# dfp1.net
KiCad netlist of a schematic drawn in EAGLE
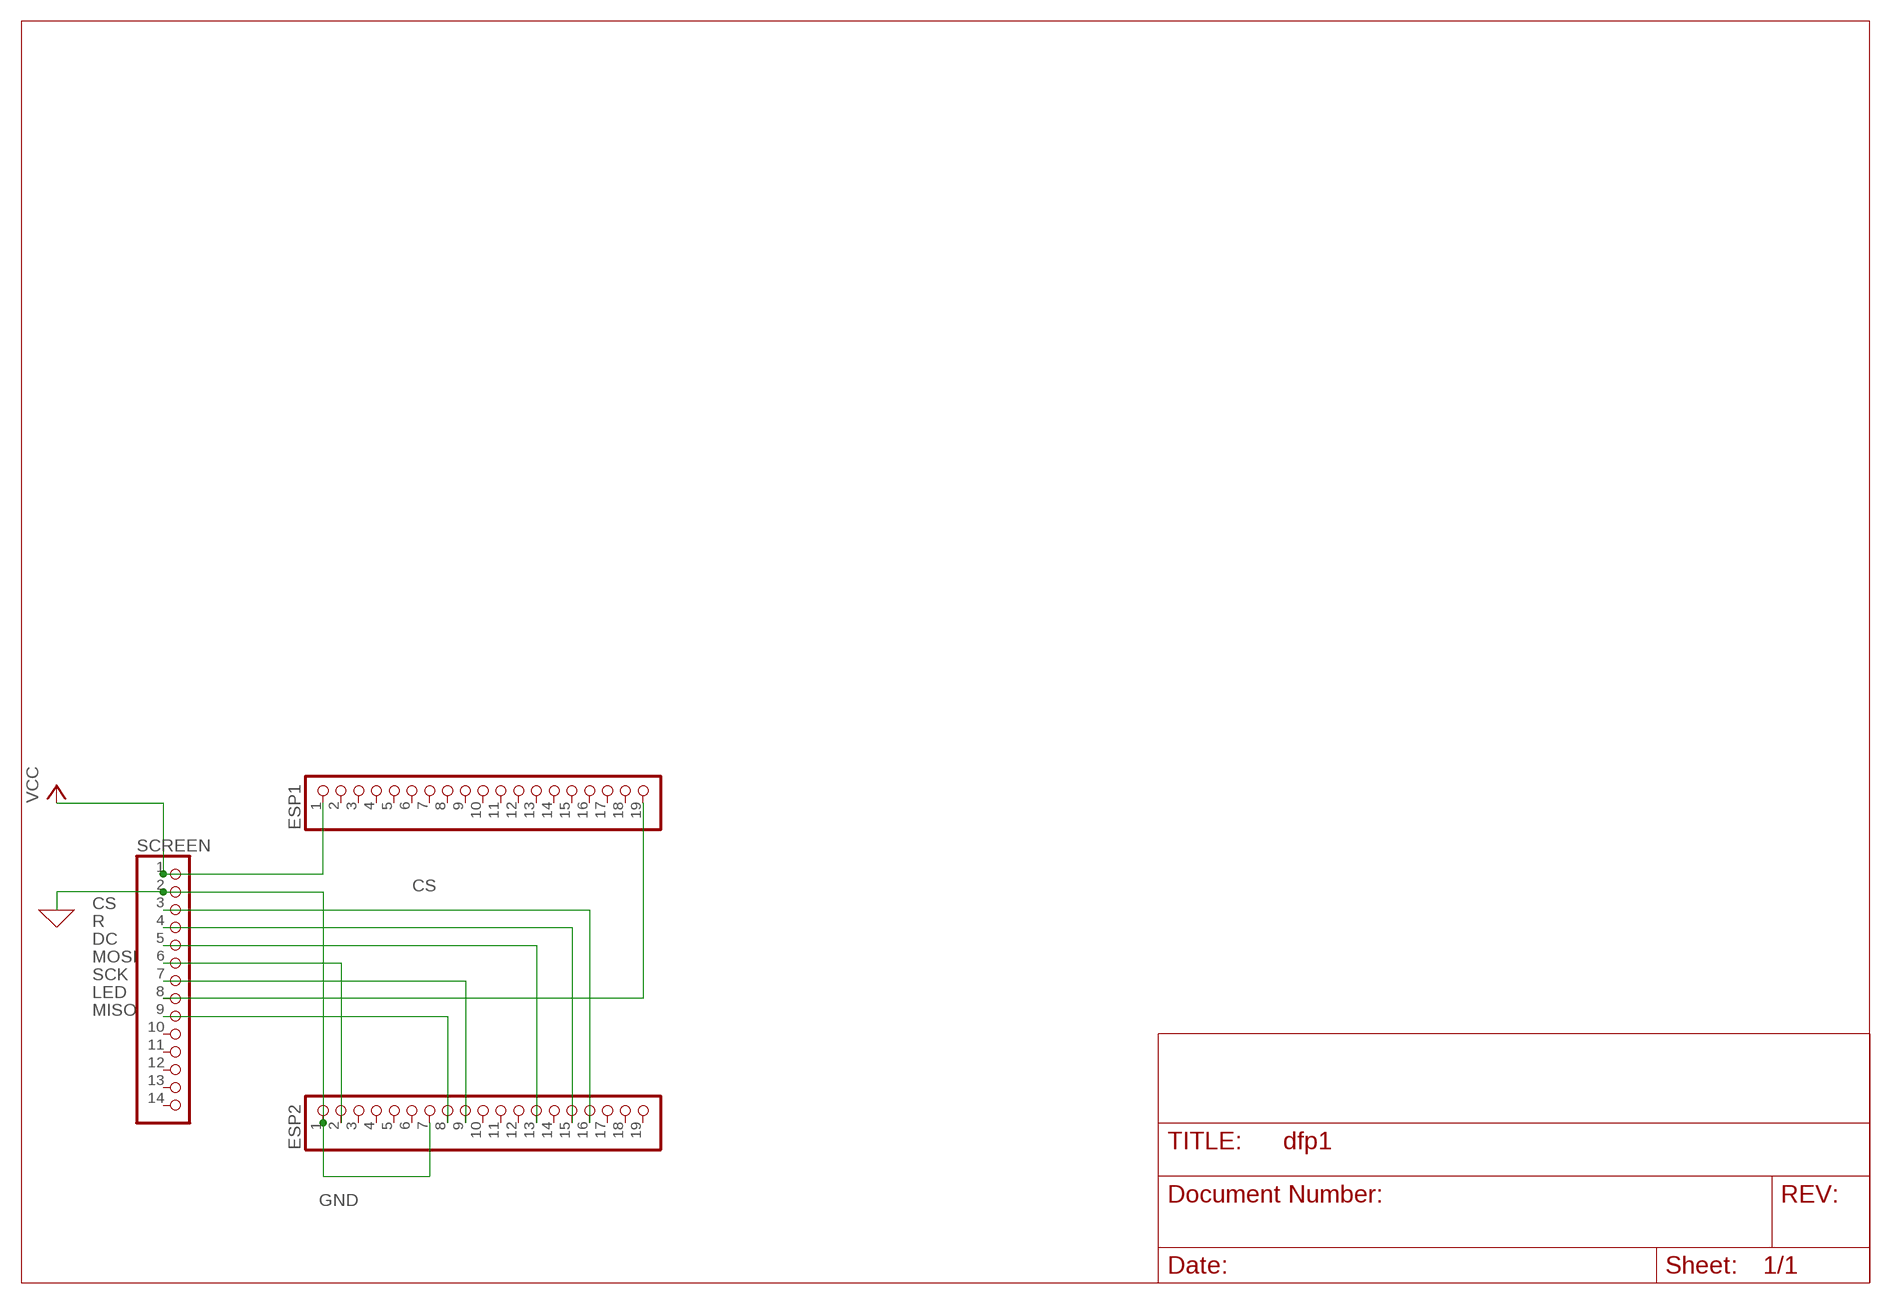
[diagram p0: schematic, sheet 1]

(export (version "E")
  (design (tool "Eeschema 10.0.6"))
  (components
    (comp (ref "ESP1")
      (value "PINHD-1X19")
      (footprint "eagle-import:1X19")
      (libsource (lib "eagle-import") (part "PINHD-1X19"))
    )
    (comp (ref "ESP2")
      (value "PINHD-1X19")
      (footprint "eagle-import:1X19")
      (libsource (lib "eagle-import") (part "PINHD-1X19"))
    )
    (comp (ref "SCREEN")
      (value "PINHD-1X14")
      (footprint "eagle-import:1X14")
      (libsource (lib "eagle-import") (part "PINHD-1X14"))
    )
  )
  (nets
    (net (code "1") (name "/CS") (class "Default")
      (node (ref "ESP2") (pin "16") (pinfunction "16_16") (pintype "passive"))
      (node (ref "SCREEN") (pin "3") (pinfunction "3_3") (pintype "passive"))
    )
    (net (code "2") (name "/DC") (class "Default")
      (node (ref "ESP2") (pin "13") (pinfunction "13_13") (pintype "passive"))
      (node (ref "SCREEN") (pin "5") (pinfunction "5_5") (pintype "passive"))
    )
    (net (code "3") (name "/LED") (class "Default")
      (node (ref "ESP1") (pin "19") (pinfunction "19_19") (pintype "passive"))
      (node (ref "SCREEN") (pin "8") (pinfunction "8_8") (pintype "passive"))
    )
    (net (code "4") (name "/MISO") (class "Default")
      (node (ref "ESP2") (pin "8") (pinfunction "8_8") (pintype "passive"))
      (node (ref "SCREEN") (pin "9") (pinfunction "9_9") (pintype "passive"))
    )
    (net (code "5") (name "/MOSI") (class "Default")
      (node (ref "ESP2") (pin "2") (pinfunction "2_2") (pintype "passive"))
      (node (ref "SCREEN") (pin "6") (pinfunction "6_6") (pintype "passive"))
    )
    (net (code "6") (name "/R") (class "Default")
      (node (ref "ESP2") (pin "15") (pinfunction "15_15") (pintype "passive"))
      (node (ref "SCREEN") (pin "4") (pinfunction "4_4") (pintype "passive"))
    )
    (net (code "7") (name "/SCK") (class "Default")
      (node (ref "ESP2") (pin "9") (pinfunction "9_9") (pintype "passive"))
      (node (ref "SCREEN") (pin "7") (pinfunction "7_7") (pintype "passive"))
    )
    (net (code "8") (name "GND") (class "Default")
      (node (ref "ESP2") (pin "1") (pinfunction "1_1") (pintype "passive"))
      (node (ref "ESP2") (pin "7") (pinfunction "7_7") (pintype "passive"))
      (node (ref "SCREEN") (pin "2") (pinfunction "2_2") (pintype "passive"))
    )
    (net (code "9") (name "VCC") (class "Default")
      (node (ref "ESP1") (pin "1") (pinfunction "1_1") (pintype "passive"))
      (node (ref "SCREEN") (pin "1") (pinfunction "1_1") (pintype "passive"))
    )
    (net (code "10") (name "unconnected-(ESP1-Pad2)") (class "Default")
      (node (ref "ESP1") (pin "2") (pinfunction "2_2") (pintype "passive"))
    )
    (net (code "11") (name "unconnected-(ESP1-Pad3)") (class "Default")
      (node (ref "ESP1") (pin "3") (pinfunction "3_3") (pintype "passive"))
    )
    (net (code "12") (name "unconnected-(ESP1-Pad4)") (class "Default")
      (node (ref "ESP1") (pin "4") (pinfunction "4_4") (pintype "passive"))
    )
    (net (code "13") (name "unconnected-(ESP1-Pad5)") (class "Default")
      (node (ref "ESP1") (pin "5") (pinfunction "5_5") (pintype "passive"))
    )
    (net (code "14") (name "unconnected-(ESP1-Pad6)") (class "Default")
      (node (ref "ESP1") (pin "6") (pinfunction "6_6") (pintype "passive"))
    )
    (net (code "15") (name "unconnected-(ESP1-Pad7)") (class "Default")
      (node (ref "ESP1") (pin "7") (pinfunction "7_7") (pintype "passive"))
    )
    (net (code "16") (name "unconnected-(ESP1-Pad8)") (class "Default")
      (node (ref "ESP1") (pin "8") (pinfunction "8_8") (pintype "passive"))
    )
    (net (code "17") (name "unconnected-(ESP1-Pad9)") (class "Default")
      (node (ref "ESP1") (pin "9") (pinfunction "9_9") (pintype "passive"))
    )
    (net (code "18") (name "unconnected-(ESP1-Pad10)") (class "Default")
      (node (ref "ESP1") (pin "10") (pinfunction "10_10") (pintype "passive"))
    )
    (net (code "19") (name "unconnected-(ESP1-Pad11)") (class "Default")
      (node (ref "ESP1") (pin "11") (pinfunction "11_11") (pintype "passive"))
    )
    (net (code "20") (name "unconnected-(ESP1-Pad12)") (class "Default")
      (node (ref "ESP1") (pin "12") (pinfunction "12_12") (pintype "passive"))
    )
    (net (code "21") (name "unconnected-(ESP1-Pad13)") (class "Default")
      (node (ref "ESP1") (pin "13") (pinfunction "13_13") (pintype "passive"))
    )
    (net (code "22") (name "unconnected-(ESP1-Pad14)") (class "Default")
      (node (ref "ESP1") (pin "14") (pinfunction "14_14") (pintype "passive"))
    )
    (net (code "23") (name "unconnected-(ESP1-Pad15)") (class "Default")
      (node (ref "ESP1") (pin "15") (pinfunction "15_15") (pintype "passive"))
    )
    (net (code "24") (name "unconnected-(ESP1-Pad16)") (class "Default")
      (node (ref "ESP1") (pin "16") (pinfunction "16_16") (pintype "passive"))
    )
    (net (code "25") (name "unconnected-(ESP1-Pad17)") (class "Default")
      (node (ref "ESP1") (pin "17") (pinfunction "17_17") (pintype "passive"))
    )
    (net (code "26") (name "unconnected-(ESP1-Pad18)") (class "Default")
      (node (ref "ESP1") (pin "18") (pinfunction "18_18") (pintype "passive"))
    )
    (net (code "27") (name "unconnected-(ESP2-Pad3)") (class "Default")
      (node (ref "ESP2") (pin "3") (pinfunction "3_3") (pintype "passive"))
    )
    (net (code "28") (name "unconnected-(ESP2-Pad4)") (class "Default")
      (node (ref "ESP2") (pin "4") (pinfunction "4_4") (pintype "passive"))
    )
    (net (code "29") (name "unconnected-(ESP2-Pad5)") (class "Default")
      (node (ref "ESP2") (pin "5") (pinfunction "5_5") (pintype "passive"))
    )
    (net (code "30") (name "unconnected-(ESP2-Pad6)") (class "Default")
      (node (ref "ESP2") (pin "6") (pinfunction "6_6") (pintype "passive"))
    )
    (net (code "31") (name "unconnected-(ESP2-Pad10)") (class "Default")
      (node (ref "ESP2") (pin "10") (pinfunction "10_10") (pintype "passive"))
    )
    (net (code "32") (name "unconnected-(ESP2-Pad11)") (class "Default")
      (node (ref "ESP2") (pin "11") (pinfunction "11_11") (pintype "passive"))
    )
    (net (code "33") (name "unconnected-(ESP2-Pad12)") (class "Default")
      (node (ref "ESP2") (pin "12") (pinfunction "12_12") (pintype "passive"))
    )
    (net (code "34") (name "unconnected-(ESP2-Pad14)") (class "Default")
      (node (ref "ESP2") (pin "14") (pinfunction "14_14") (pintype "passive"))
    )
    (net (code "35") (name "unconnected-(ESP2-Pad17)") (class "Default")
      (node (ref "ESP2") (pin "17") (pinfunction "17_17") (pintype "passive"))
    )
    (net (code "36") (name "unconnected-(ESP2-Pad18)") (class "Default")
      (node (ref "ESP2") (pin "18") (pinfunction "18_18") (pintype "passive"))
    )
    (net (code "37") (name "unconnected-(ESP2-Pad19)") (class "Default")
      (node (ref "ESP2") (pin "19") (pinfunction "19_19") (pintype "passive"))
    )
    (net (code "38") (name "unconnected-(SCREEN-Pad10)") (class "Default")
      (node (ref "SCREEN") (pin "10") (pinfunction "10_10") (pintype "passive"))
    )
    (net (code "39") (name "unconnected-(SCREEN-Pad11)") (class "Default")
      (node (ref "SCREEN") (pin "11") (pinfunction "11_11") (pintype "passive"))
    )
    (net (code "40") (name "unconnected-(SCREEN-Pad12)") (class "Default")
      (node (ref "SCREEN") (pin "12") (pinfunction "12_12") (pintype "passive"))
    )
    (net (code "41") (name "unconnected-(SCREEN-Pad13)") (class "Default")
      (node (ref "SCREEN") (pin "13") (pinfunction "13_13") (pintype "passive"))
    )
    (net (code "42") (name "unconnected-(SCREEN-Pad14)") (class "Default")
      (node (ref "SCREEN") (pin "14") (pinfunction "14_14") (pintype "passive"))
    )
  )
)
